# SOLv1_0.net
KiCad netlist of a schematic drawn in EAGLE
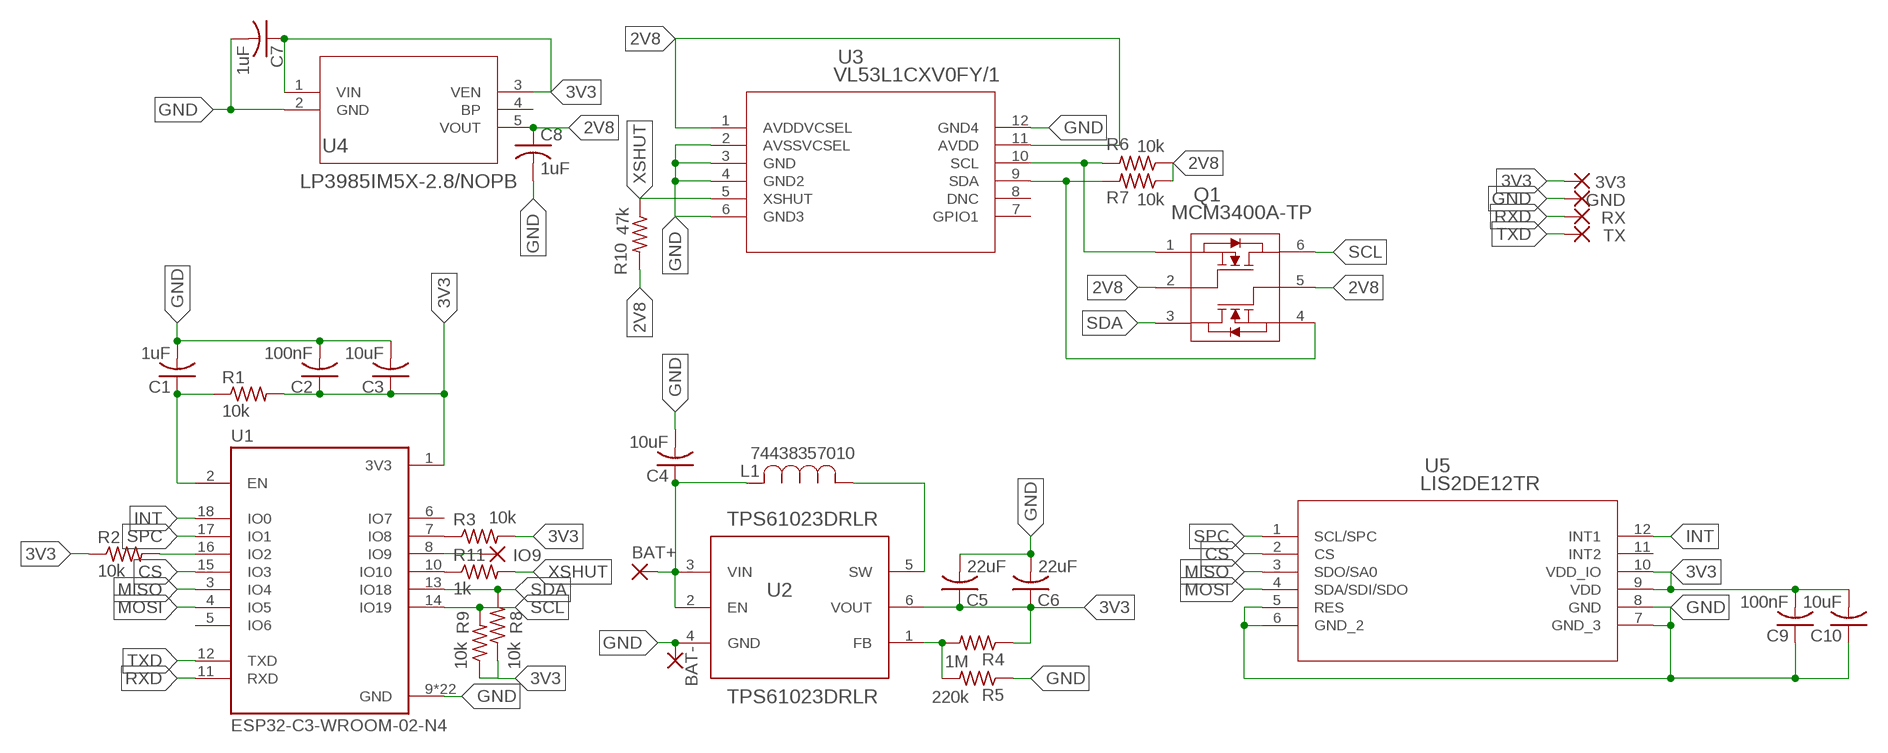
[diagram p0: schematic, sheet 1]

(export (version "E")
  (design (tool "Eeschema 10.0.6"))
  (components
    (comp (ref "3V3")
      (value "1,6/0,8")
      (footprint "eagle-import:1,6_0,8")
      (libsource (lib "eagle-import") (part "1,6/0,8"))
    )
    (comp (ref "BAT+")
      (value "1,6/0,8")
      (footprint "eagle-import:1,6_0,8")
      (libsource (lib "eagle-import") (part "1,6/0,8"))
    )
    (comp (ref "BAT-")
      (value "1,6/0,8")
      (footprint "eagle-import:1,6_0,8")
      (libsource (lib "eagle-import") (part "1,6/0,8"))
    )
    (comp (ref "C1")
      (value "1uF")
      (footprint "eagle-import:C0805")
      (libsource (lib "eagle-import") (part "C-USC0805"))
    )
    (comp (ref "C2")
      (value "100nF")
      (footprint "eagle-import:C0805")
      (libsource (lib "eagle-import") (part "C-USC0805"))
    )
    (comp (ref "C3")
      (value "10uF")
      (footprint "eagle-import:C0805")
      (libsource (lib "eagle-import") (part "C-USC0805"))
    )
    (comp (ref "C4")
      (value "10uF")
      (footprint "eagle-import:C0805")
      (libsource (lib "eagle-import") (part "C-USC0805"))
    )
    (comp (ref "C5")
      (value "22uF")
      (footprint "eagle-import:C0805")
      (libsource (lib "eagle-import") (part "C-USC0805"))
    )
    (comp (ref "C6")
      (value "22uF")
      (footprint "eagle-import:C0805")
      (libsource (lib "eagle-import") (part "C-USC0805"))
    )
    (comp (ref "C7")
      (value "1uF")
      (footprint "eagle-import:C0805")
      (libsource (lib "eagle-import") (part "C-USC0805"))
    )
    (comp (ref "C8")
      (value "1uF")
      (footprint "eagle-import:C0805")
      (libsource (lib "eagle-import") (part "C-USC0805"))
    )
    (comp (ref "C9")
      (value "100nF")
      (footprint "eagle-import:C0805")
      (libsource (lib "eagle-import") (part "C-USC0805"))
    )
    (comp (ref "C10")
      (value "10uF")
      (footprint "eagle-import:C0805")
      (libsource (lib "eagle-import") (part "C-USC0805"))
    )
    (comp (ref "GND")
      (value "1,6/0,8")
      (footprint "eagle-import:1,6_0,8")
      (libsource (lib "eagle-import") (part "1,6/0,8"))
    )
    (comp (ref "IO9")
      (value "1,6/0,8")
      (footprint "eagle-import:1,6_0,8")
      (libsource (lib "eagle-import") (part "1,6/0,8"))
    )
    (comp (ref "L1")
      (value "74438357010")
      (footprint "eagle-import:IND_74438357010_WRE")
      (fields (field (name "COPYRIGHT") "Copyright (C) 2024 Ultra Librarian. All rights reserved."))
      (libsource (lib "eagle-import") (part "74438357010"))
    )
    (comp (ref "Q1")
      (value "MCM3400A-TP")
      (footprint "eagle-import:DFN2020-6L_MCE")
      (fields (field (name "COPYRIGHT") "Copyright (C) 2024 Ultra Librarian. All rights reserved."))
      (libsource (lib "eagle-import") (part "MCM3400A-TP"))
    )
    (comp (ref "R1")
      (value "10k")
      (footprint "eagle-import:R0805")
      (libsource (lib "eagle-import") (part "R-US_R0805"))
    )
    (comp (ref "R2")
      (value "10k")
      (footprint "eagle-import:R0805")
      (libsource (lib "eagle-import") (part "R-US_R0805"))
    )
    (comp (ref "R3")
      (value "10k")
      (footprint "eagle-import:R0805")
      (libsource (lib "eagle-import") (part "R-US_R0805"))
    )
    (comp (ref "R4")
      (value "1M")
      (footprint "eagle-import:R0805")
      (libsource (lib "eagle-import") (part "R-US_R0805"))
    )
    (comp (ref "R5")
      (value "220k")
      (footprint "eagle-import:R0805")
      (libsource (lib "eagle-import") (part "R-US_R0805"))
    )
    (comp (ref "R6")
      (value "10k")
      (footprint "eagle-import:R0805")
      (libsource (lib "eagle-import") (part "R-US_R0805"))
    )
    (comp (ref "R7")
      (value "10k")
      (footprint "eagle-import:R0805")
      (libsource (lib "eagle-import") (part "R-US_R0805"))
    )
    (comp (ref "R8")
      (value "10k")
      (footprint "eagle-import:R0805")
      (libsource (lib "eagle-import") (part "R-US_R0805"))
    )
    (comp (ref "R9")
      (value "10k")
      (footprint "eagle-import:R0805")
      (libsource (lib "eagle-import") (part "R-US_R0805"))
    )
    (comp (ref "R10")
      (value "47k")
      (footprint "eagle-import:R0805")
      (libsource (lib "eagle-import") (part "R-US_R0805"))
    )
    (comp (ref "R11")
      (value "1k")
      (footprint "eagle-import:R0805")
      (libsource (lib "eagle-import") (part "R-US_R0805"))
    )
    (comp (ref "RX")
      (value "1,6/0,8")
      (footprint "eagle-import:1,6_0,8")
      (libsource (lib "eagle-import") (part "1,6/0,8"))
    )
    (comp (ref "TX")
      (value "1,6/0,8")
      (footprint "eagle-import:1,6_0,8")
      (libsource (lib "eagle-import") (part "1,6/0,8"))
    )
    (comp (ref "U1")
      (value "ESP32-C3-WROOM-02-N4")
      (footprint "eagle-import:MODULE_ESP32-C3-WROOM-02-H4")
      (fields (field (name "MF") "Espressif Systems"))
      (libsource (lib "eagle-import") (part "ESP32-C3-WROOM-02-N4"))
    )
    (comp (ref "U2")
      (value "TPS61023DRLR")
      (footprint "eagle-import:DRL0006A")
      (fields (field (name "COPYRIGHT") "Copyright (C) 2024 Ultra Librarian. All rights reserved."))
      (libsource (lib "eagle-import") (part "TPS61023DRLR"))
    )
    (comp (ref "U3")
      (value "VL53L1CXV0FY/1")
      (footprint "eagle-import:LGA12_STM")
      (fields (field (name "COPYRIGHT") "Copyright (C) 2024 Ultra Librarian. All rights reserved."))
      (libsource (lib "eagle-import") (part "VL53L1CXV0FY/1"))
    )
    (comp (ref "U4")
      (value "LP3985IM5X-2.8/NOPB")
      (footprint "eagle-import:MF05A")
      (fields (field (name "COPYRIGHT") "Copyright (C) 2024 Ultra Librarian. All rights reserved."))
      (libsource (lib "eagle-import") (part "LP3985IM5X-2.8/NOPB"))
    )
    (comp (ref "U5")
      (value "LIS2DE12TR")
      (footprint "eagle-import:LGA-12_STM")
      (fields (field (name "COPYRIGHT") "Copyright (C) 2024 Ultra Librarian. All rights reserved."))
      (libsource (lib "eagle-import") (part "LIS2DE12TR"))
    )
  )
  (nets
    (net (code "1") (name "2V8") (class "Default")
      (node (ref "C8") (pin "1") (pinfunction "1_1") (pintype "passive"))
      (node (ref "Q1") (pin "2") (pinfunction "2_2") (pintype "passive"))
      (node (ref "Q1") (pin "5") (pinfunction "5_5") (pintype "passive"))
      (node (ref "R10") (pin "2") (pinfunction "2_2") (pintype "passive"))
      (node (ref "R6") (pin "1") (pinfunction "1_1") (pintype "passive"))
      (node (ref "R7") (pin "1") (pinfunction "1_1") (pintype "passive"))
      (node (ref "U3") (pin "1") (pinfunction "AVDDVCSEL_1") (pintype "power_in"))
      (node (ref "U3") (pin "11") (pinfunction "AVDD_11") (pintype "power_in"))
      (node (ref "U4") (pin "5") (pinfunction "VOUT_5") (pintype "output"))
    )
    (net (code "2") (name "3V3") (class "Default")
      (node (ref "3V3") (pin "1") (pinfunction "P_1") (pintype "passive"))
      (node (ref "C10") (pin "2") (pinfunction "2_2") (pintype "passive"))
      (node (ref "C2") (pin "1") (pinfunction "1_1") (pintype "passive"))
      (node (ref "C3") (pin "1") (pinfunction "1_1") (pintype "passive"))
      (node (ref "C5") (pin "1") (pinfunction "1_1") (pintype "passive"))
      (node (ref "C6") (pin "1") (pinfunction "1_1") (pintype "passive"))
      (node (ref "C7") (pin "1") (pinfunction "1_1") (pintype "passive"))
      (node (ref "C9") (pin "2") (pinfunction "2_2") (pintype "passive"))
      (node (ref "R1") (pin "2") (pinfunction "2_2") (pintype "passive"))
      (node (ref "R2") (pin "1") (pinfunction "1_1") (pintype "passive"))
      (node (ref "R3") (pin "2") (pinfunction "2_2") (pintype "passive"))
      (node (ref "R4") (pin "1") (pinfunction "1_1") (pintype "passive"))
      (node (ref "R8") (pin "1") (pinfunction "1_1") (pintype "passive"))
      (node (ref "R9") (pin "1") (pinfunction "1_1") (pintype "passive"))
      (node (ref "U1") (pin "1") (pinfunction "3V3_1") (pintype "power_in"))
      (node (ref "U2") (pin "6") (pinfunction "VOUT_6") (pintype "power_in"))
      (node (ref "U4") (pin "1") (pinfunction "VIN_1") (pintype "input"))
      (node (ref "U4") (pin "3") (pinfunction "VEN_3") (pintype "passive"))
      (node (ref "U5") (pin "10") (pinfunction "VDD_IO_10") (pintype "power_in"))
      (node (ref "U5") (pin "9") (pinfunction "VDD_9") (pintype "power_in"))
    )
    (net (code "3") (name "CS") (class "Default")
      (node (ref "U1") (pin "15") (pinfunction "IO3_15") (pintype "bidirectional"))
      (node (ref "U5") (pin "2") (pinfunction "CS_2") (pintype "input"))
    )
    (net (code "4") (name "GND") (class "Default")
      (node (ref "BAT-") (pin "1") (pinfunction "P_1") (pintype "passive"))
      (node (ref "C1") (pin "2") (pinfunction "2_2") (pintype "passive"))
      (node (ref "C10") (pin "1") (pinfunction "1_1") (pintype "passive"))
      (node (ref "C2") (pin "2") (pinfunction "2_2") (pintype "passive"))
      (node (ref "C3") (pin "2") (pinfunction "2_2") (pintype "passive"))
      (node (ref "C4") (pin "2") (pinfunction "2_2") (pintype "passive"))
      (node (ref "C5") (pin "2") (pinfunction "2_2") (pintype "passive"))
      (node (ref "C6") (pin "2") (pinfunction "2_2") (pintype "passive"))
      (node (ref "C7") (pin "2") (pinfunction "2_2") (pintype "passive"))
      (node (ref "C8") (pin "2") (pinfunction "2_2") (pintype "passive"))
      (node (ref "C9") (pin "1") (pinfunction "1_1") (pintype "passive"))
      (node (ref "GND") (pin "1") (pinfunction "P_1") (pintype "passive"))
      (node (ref "R5") (pin "1") (pinfunction "1_1") (pintype "passive"))
      (node (ref "U1") (pin "19") (pinfunction "GND_19") (pintype "power_in"))
      (node (ref "U1") (pin "20") (pinfunction "GND_20") (pintype "power_in"))
      (node (ref "U1") (pin "21") (pinfunction "GND_21") (pintype "power_in"))
      (node (ref "U1") (pin "22") (pinfunction "GND_22") (pintype "power_in"))
      (node (ref "U1") (pin "23") (pinfunction "GND_23") (pintype "power_in"))
      (node (ref "U1") (pin "24") (pinfunction "GND_24") (pintype "power_in"))
      (node (ref "U1") (pin "25") (pinfunction "GND_25") (pintype "power_in"))
      (node (ref "U1") (pin "26") (pinfunction "GND_26") (pintype "power_in"))
      (node (ref "U1") (pin "27") (pinfunction "GND_27") (pintype "power_in"))
      (node (ref "U1") (pin "28") (pinfunction "GND_28") (pintype "power_in"))
      (node (ref "U1") (pin "29") (pinfunction "GND_29") (pintype "power_in"))
      (node (ref "U1") (pin "30") (pinfunction "GND_30") (pintype "power_in"))
      (node (ref "U1") (pin "31") (pinfunction "GND_31") (pintype "power_in"))
      (node (ref "U1") (pin "32") (pinfunction "GND_32") (pintype "power_in"))
      (node (ref "U1") (pin "33") (pinfunction "GND_33") (pintype "power_in"))
      (node (ref "U1") (pin "34") (pinfunction "GND_34") (pintype "power_in"))
      (node (ref "U1") (pin "35") (pinfunction "GND_35") (pintype "power_in"))
      (node (ref "U1") (pin "36") (pinfunction "GND_36") (pintype "power_in"))
      (node (ref "U1") (pin "37") (pinfunction "GND_37") (pintype "power_in"))
      (node (ref "U1") (pin "38") (pinfunction "GND_38") (pintype "power_in"))
      (node (ref "U1") (pin "39") (pinfunction "GND_39") (pintype "power_in"))
      (node (ref "U1") (pin "9") (pinfunction "GND_9") (pintype "power_in"))
      (node (ref "U2") (pin "4") (pinfunction "GND_4") (pintype "power_in"))
      (node (ref "U3") (pin "12") (pinfunction "GND4_12") (pintype "power_in"))
      (node (ref "U3") (pin "2") (pinfunction "AVSSVCSEL_2") (pintype "power_in"))
      (node (ref "U3") (pin "3") (pinfunction "GND_3") (pintype "power_in"))
      (node (ref "U3") (pin "4") (pinfunction "GND2_4") (pintype "power_in"))
      (node (ref "U3") (pin "6") (pinfunction "GND3_6") (pintype "power_in"))
      (node (ref "U4") (pin "2") (pinfunction "GND_2") (pintype "passive"))
      (node (ref "U5") (pin "5") (pinfunction "RES_5") (pintype "passive"))
      (node (ref "U5") (pin "6") (pinfunction "GND_2_6") (pintype "passive"))
      (node (ref "U5") (pin "7") (pinfunction "GND_3_7") (pintype "passive"))
      (node (ref "U5") (pin "8") (pinfunction "GND_8") (pintype "passive"))
    )
    (net (code "5") (name "INT") (class "Default")
      (node (ref "U1") (pin "18") (pinfunction "IO0_18") (pintype "bidirectional"))
      (node (ref "U5") (pin "12") (pinfunction "INT1_12") (pintype "bidirectional"))
    )
    (net (code "6") (name "MISO") (class "Default")
      (node (ref "U1") (pin "3") (pinfunction "IO4_3") (pintype "bidirectional"))
      (node (ref "U5") (pin "3") (pinfunction "SDO/SA0_3") (pintype "bidirectional"))
    )
    (net (code "7") (name "MOSI") (class "Default")
      (node (ref "U1") (pin "4") (pinfunction "IO5_4") (pintype "bidirectional"))
      (node (ref "U5") (pin "4") (pinfunction "SDA/SDI/SDO_4") (pintype "bidirectional"))
    )
    (net (code "8") (name "Net-(BAT+-P)") (class "Default")
      (node (ref "BAT+") (pin "1") (pinfunction "P_1") (pintype "passive"))
      (node (ref "C4") (pin "1") (pinfunction "1_1") (pintype "passive"))
      (node (ref "L1") (pin "2") (pinfunction "2_2") (pintype "passive"))
      (node (ref "U2") (pin "2") (pinfunction "EN_2") (pintype "input"))
      (node (ref "U2") (pin "3") (pinfunction "VIN_3") (pintype "power_in"))
    )
    (net (code "9") (name "Net-(IO9-P)") (class "Default")
      (node (ref "IO9") (pin "1") (pinfunction "P_1") (pintype "passive"))
      (node (ref "U1") (pin "8") (pinfunction "IO9_8") (pintype "bidirectional"))
    )
    (net (code "10") (name "Net-(U1-EN)") (class "Default")
      (node (ref "C1") (pin "1") (pinfunction "1_1") (pintype "passive"))
      (node (ref "R1") (pin "1") (pinfunction "1_1") (pintype "passive"))
      (node (ref "U1") (pin "2") (pinfunction "EN_2") (pintype "input"))
    )
    (net (code "11") (name "Net-(U1-IO2)") (class "Default")
      (node (ref "R2") (pin "2") (pinfunction "2_2") (pintype "passive"))
      (node (ref "U1") (pin "16") (pinfunction "IO2_16") (pintype "bidirectional"))
    )
    (net (code "12") (name "Net-(U1-IO8)") (class "Default")
      (node (ref "R3") (pin "1") (pinfunction "1_1") (pintype "passive"))
      (node (ref "U1") (pin "7") (pinfunction "IO8_7") (pintype "bidirectional"))
    )
    (net (code "13") (name "Net-(U1-IO10)") (class "Default")
      (node (ref "R11") (pin "1") (pinfunction "1_1") (pintype "passive"))
      (node (ref "U1") (pin "10") (pinfunction "IO10_10") (pintype "bidirectional"))
    )
    (net (code "14") (name "Net-(U2-FB)") (class "Default")
      (node (ref "R4") (pin "2") (pinfunction "2_2") (pintype "passive"))
      (node (ref "R5") (pin "2") (pinfunction "2_2") (pintype "passive"))
      (node (ref "U2") (pin "1") (pinfunction "FB_1") (pintype "input"))
    )
    (net (code "15") (name "Net-(U2-SW)") (class "Default")
      (node (ref "L1") (pin "1") (pinfunction "1_1") (pintype "passive"))
      (node (ref "U2") (pin "5") (pinfunction "SW_5") (pintype "power_in"))
    )
    (net (code "16") (name "Net-(U3-SCL)") (class "Default")
      (node (ref "Q1") (pin "1") (pinfunction "1_1") (pintype "passive"))
      (node (ref "R6") (pin "2") (pinfunction "2_2") (pintype "passive"))
      (node (ref "U3") (pin "10") (pinfunction "SCL_10") (pintype "input"))
    )
    (net (code "17") (name "Net-(U3-SDA)") (class "Default")
      (node (ref "Q1") (pin "4") (pinfunction "4_4") (pintype "passive"))
      (node (ref "R7") (pin "2") (pinfunction "2_2") (pintype "passive"))
      (node (ref "U3") (pin "9") (pinfunction "SDA_9") (pintype "bidirectional"))
    )
    (net (code "18") (name "RXD") (class "Default")
      (node (ref "RX") (pin "1") (pinfunction "P_1") (pintype "passive"))
      (node (ref "U1") (pin "11") (pinfunction "RXD_11") (pintype "bidirectional"))
    )
    (net (code "19") (name "SCL") (class "Default")
      (node (ref "Q1") (pin "6") (pinfunction "6_6") (pintype "passive"))
      (node (ref "R9") (pin "2") (pinfunction "2_2") (pintype "passive"))
      (node (ref "U1") (pin "14") (pinfunction "IO19_14") (pintype "bidirectional"))
    )
    (net (code "20") (name "SDA") (class "Default")
      (node (ref "Q1") (pin "3") (pinfunction "3_3") (pintype "passive"))
      (node (ref "R8") (pin "2") (pinfunction "2_2") (pintype "passive"))
      (node (ref "U1") (pin "13") (pinfunction "IO18_13") (pintype "bidirectional"))
    )
    (net (code "21") (name "SPC") (class "Default")
      (node (ref "U1") (pin "17") (pinfunction "IO1_17") (pintype "bidirectional"))
      (node (ref "U5") (pin "1") (pinfunction "SCL/SPC_1") (pintype "input"))
    )
    (net (code "22") (name "TXD") (class "Default")
      (node (ref "TX") (pin "1") (pinfunction "P_1") (pintype "passive"))
      (node (ref "U1") (pin "12") (pinfunction "TXD_12") (pintype "bidirectional"))
    )
    (net (code "23") (name "XSHUT") (class "Default")
      (node (ref "R10") (pin "1") (pinfunction "1_1") (pintype "passive"))
      (node (ref "R11") (pin "2") (pinfunction "2_2") (pintype "passive"))
      (node (ref "U3") (pin "5") (pinfunction "XSHUT_5") (pintype "input"))
    )
    (net (code "24") (name "unconnected-(U1-IO6-Pad5)") (class "Default")
      (node (ref "U1") (pin "5") (pinfunction "IO6_5") (pintype "bidirectional"))
    )
    (net (code "25") (name "unconnected-(U1-IO7-Pad6)") (class "Default")
      (node (ref "U1") (pin "6") (pinfunction "IO7_6") (pintype "bidirectional"))
    )
    (net (code "26") (name "unconnected-(U3-DNC-Pad8)") (class "Default")
      (node (ref "U3") (pin "8") (pinfunction "DNC_8") (pintype "no_connect"))
    )
    (net (code "27") (name "unconnected-(U3-GPIO1-Pad7)") (class "Default")
      (node (ref "U3") (pin "7") (pinfunction "GPIO1_7") (pintype "bidirectional"))
    )
    (net (code "28") (name "unconnected-(U4-BP-Pad4)") (class "Default")
      (node (ref "U4") (pin "4") (pinfunction "BP_4") (pintype "passive"))
    )
    (net (code "29") (name "unconnected-(U5-INT2-Pad11)") (class "Default")
      (node (ref "U5") (pin "11") (pinfunction "INT2_11") (pintype "bidirectional"))
    )
  )
)
